# dolinesch.net
KiCad netlist of a schematic drawn in Altium Designer
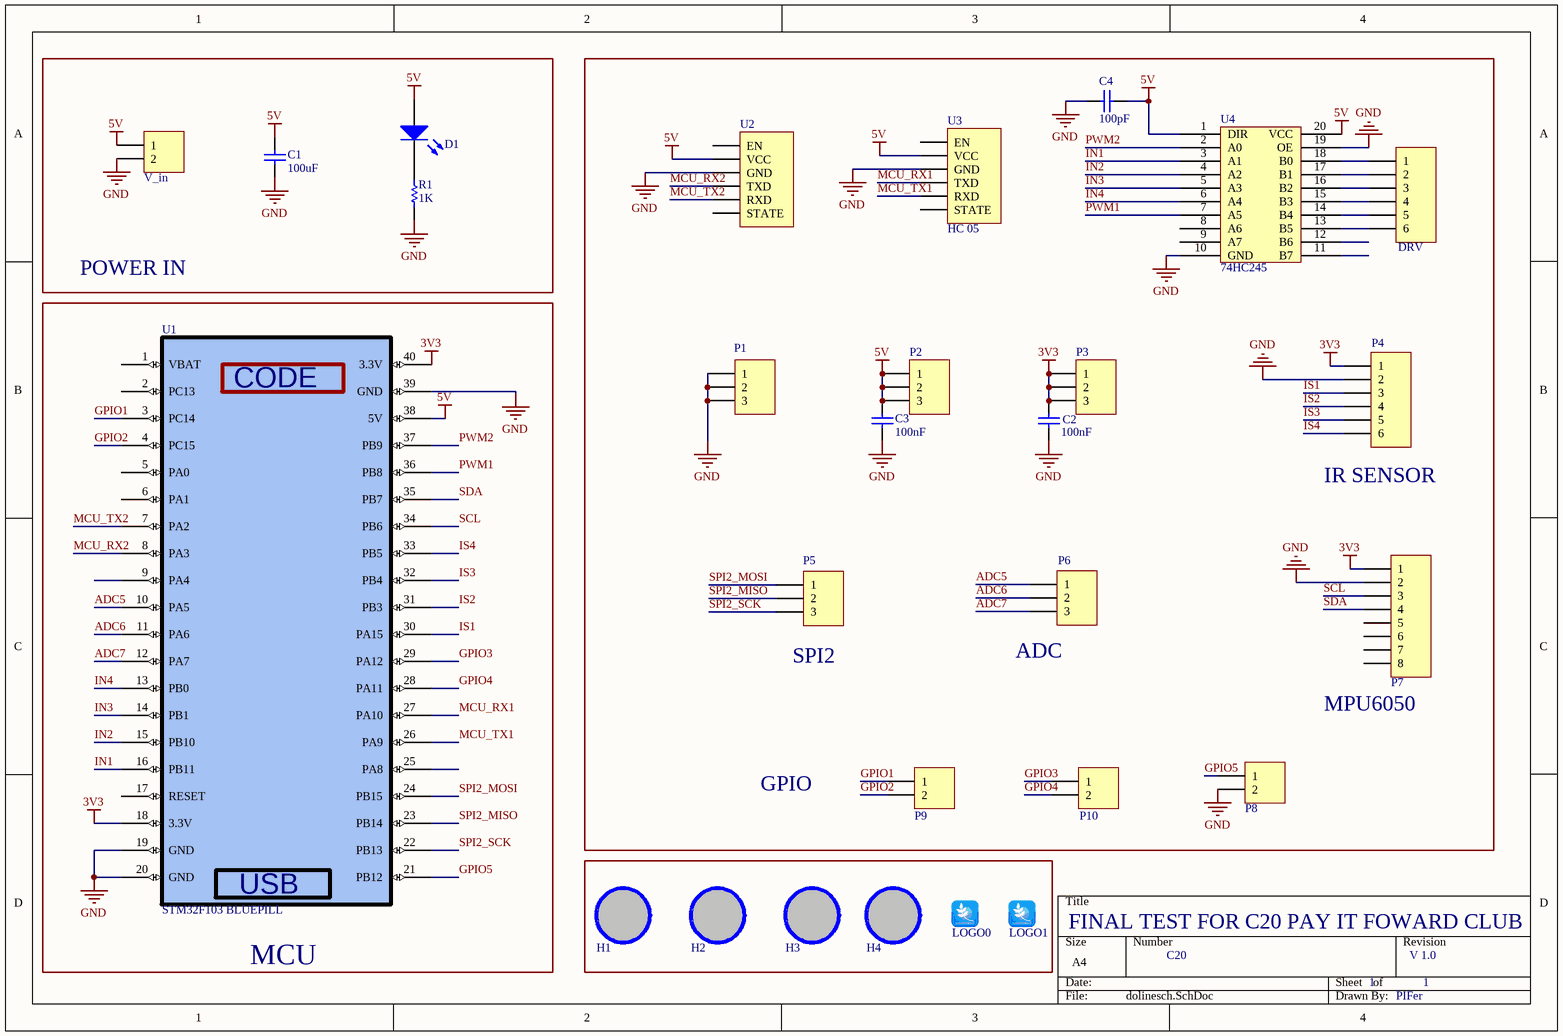
[diagram p0: dolinesch.SchDoc]

(export (version "E")
  (design (tool "Eeschema 10.0.6"))
  (components
    (comp (ref "C1")
      (value "100uF")
      (footprint "CAP-SM-0805")
      (description "Capacitor")
      (fields (field (name "Comment") "Cap Non-Pol SMD"))
      (libsource (lib "PIF_Schematic_Lib") (part "Cap Non-Pol SMD"))
    )
    (comp (ref "C2")
      (value "100nF")
      (footprint "CAP-SM-0805")
      (description "Capacitor")
      (fields (field (name "Comment") "Cap Non-Pol SMD"))
      (libsource (lib "PIF_Schematic_Lib") (part "Cap Non-Pol SMD"))
    )
    (comp (ref "C3")
      (value "100nF")
      (footprint "CAP-SM-0805")
      (description "Capacitor")
      (fields (field (name "Comment") "Cap Non-Pol SMD"))
      (libsource (lib "PIF_Schematic_Lib") (part "Cap Non-Pol SMD"))
    )
    (comp (ref "C4")
      (value "100pF")
      (footprint "CAP-SM-0805")
      (description "Capacitor")
      (fields (field (name "Comment") "Cap Non-Pol SMD"))
      (libsource (lib "PIF_Schematic_Lib") (part "Cap Non-Pol SMD"))
    )
    (comp (ref "D1") (value "LED") (footprint "LED-3mm") (libsource (lib "PIF_Schematic_Lib") (part "LED")))
    (comp (ref "DRV")
      (value "Header 6")
      (footprint "JP6")
      (description "Header, 6-Pin")
      (fields (field (name "PUBLISHER") "Altium Limited"))
      (libsource (lib "PIF_Schematic_Lib") (part "Header 6"))
    )
    (comp (ref "H1")
      (value "Hole")
      (footprint "LO KHOAN 3MM")
      (description "Hole 3mm")
      (libsource (lib "PIF_Schematic_Lib") (part "Hole"))
    )
    (comp (ref "H2")
      (value "Hole")
      (footprint "LO KHOAN 3MM")
      (description "Hole 3mm")
      (libsource (lib "PIF_Schematic_Lib") (part "Hole"))
    )
    (comp (ref "H3")
      (value "Hole")
      (footprint "LO KHOAN 3MM")
      (description "Hole 3mm")
      (libsource (lib "PIF_Schematic_Lib") (part "Hole"))
    )
    (comp (ref "H4")
      (value "Hole")
      (footprint "LO KHOAN 3MM")
      (description "Hole 3mm")
      (libsource (lib "PIF_Schematic_Lib") (part "Hole"))
    )
    (comp (ref "LOGO0")
      (value "LOGO PIF")
      (footprint "PIF LOGO BOTTOM LAYER")
      (libsource (lib "PIF_Schematic_Lib") (part "LOGO PIF_2"))
    )
    (comp (ref "LOGO1")
      (value "LOGO PIF")
      (footprint "PIF LOGO TOP OVERLAY")
      (libsource (lib "PIF_Schematic_Lib") (part "LOGO PIF_2"))
    )
    (comp (ref "P1")
      (value "Header 3")
      (footprint "JP3")
      (description "Header, 3-Pin")
      (fields (field (name "PUBLISHER") "Altium Limited"))
      (libsource (lib "PIF_Schematic_Lib") (part "Header 3"))
    )
    (comp (ref "P2")
      (value "Header 3")
      (footprint "JP3")
      (description "Header, 3-Pin")
      (fields (field (name "PUBLISHER") "Altium Limited"))
      (libsource (lib "PIF_Schematic_Lib") (part "Header 3"))
    )
    (comp (ref "P3")
      (value "Header 3")
      (footprint "JP3")
      (description "Header, 3-Pin")
      (fields (field (name "PUBLISHER") "Altium Limited"))
      (libsource (lib "PIF_Schematic_Lib") (part "Header 3"))
    )
    (comp (ref "P4")
      (value "Header 6")
      (footprint "JP6")
      (description "Header, 6-Pin")
      (fields (field (name "PUBLISHER") "Altium Limited"))
      (libsource (lib "PIF_Schematic_Lib") (part "Header 6"))
    )
    (comp (ref "P5")
      (value "Header 3")
      (footprint "JP3")
      (description "Header, 3-Pin")
      (fields (field (name "PUBLISHER") "Altium Limited"))
      (libsource (lib "PIF_Schematic_Lib") (part "Header 3"))
    )
    (comp (ref "P6")
      (value "Header 3")
      (footprint "JP3")
      (description "Header, 3-Pin")
      (fields (field (name "PUBLISHER") "Altium Limited"))
      (libsource (lib "PIF_Schematic_Lib") (part "Header 3"))
    )
    (comp (ref "P7")
      (value "Header 8")
      (footprint "JP8")
      (description "Header, 8-Pin")
      (fields (field (name "PUBLISHER") "Altium Limited"))
      (libsource (lib "PIF_Schematic_Lib") (part "Header 8"))
    )
    (comp (ref "P8")
      (value "Header 2")
      (footprint "JP2")
      (description "Header, 2-Pin")
      (fields (field (name "PUBLISHER") "Altium Limited"))
      (libsource (lib "PIF_Schematic_Lib") (part "Header 2"))
    )
    (comp (ref "P9")
      (value "Header 2")
      (footprint "JP2")
      (description "Header, 2-Pin")
      (fields (field (name "PUBLISHER") "Altium Limited"))
      (libsource (lib "PIF_Schematic_Lib") (part "Header 2"))
    )
    (comp (ref "P10")
      (value "Header 2")
      (footprint "JP2")
      (description "Header, 2-Pin")
      (fields (field (name "PUBLISHER") "Altium Limited"))
      (libsource (lib "PIF_Schematic_Lib") (part "Header 2"))
    )
    (comp (ref "R1")
      (value "1K")
      (footprint "RES-SM-0603")
      (description "Resistor")
      (fields (field (name "Comment") "RESISTOR SMD"))
      (libsource (lib "PIF_Schematic_Lib") (part "RESISTOR SMD"))
    )
    (comp (ref "U1")
      (value "STM32F103 BLUEPILL")
      (footprint "STM32F103 Bluepill")
      (libsource (lib "PIF_Schematic_Lib") (part "STM32F103 BLUEPILL"))
    )
    (comp (ref "U2") (value "UART") (footprint "JP6") (libsource (lib "PIF_Schematic_Lib") (part "HC 05")))
    (comp (ref "U3") (value "HC 05") (footprint "JP6") (libsource (lib "PIF_Schematic_Lib") (part "HC 05")))
    (comp (ref "U4")
      (value "74HC245")
      (footprint "DIP20/W0.3")
      (description "Octal bus tranceiver")
      (libsource (lib "PIF_Schematic_Lib") (part "74HC245"))
    )
    (comp (ref "V_in")
      (value "Domino 2")
      (footprint "DOMINO 2- 5mm")
      (description "Domino, 2-Pin")
      (fields (field (name "PUBLISHER") "Altium Limited"))
      (libsource (lib "linecarc20_balancing") (part "Domino 2"))
    )
  )
  (nets
    (net (code "1") (name "/ADC5") (class "Default")
      (node (ref "P6") (pin "1") (pinfunction "1_1") (pintype "passive"))
      (node (ref "U1") (pin "10") (pinfunction "PA5_10") (pintype "bidirectional"))
    )
    (net (code "2") (name "/ADC6") (class "Default")
      (node (ref "P6") (pin "2") (pinfunction "2_2") (pintype "passive"))
      (node (ref "U1") (pin "11") (pinfunction "PA6_11") (pintype "bidirectional"))
    )
    (net (code "3") (name "/ADC7") (class "Default")
      (node (ref "P6") (pin "3") (pinfunction "3_3") (pintype "passive"))
      (node (ref "U1") (pin "12") (pinfunction "PA7_12") (pintype "bidirectional"))
    )
    (net (code "4") (name "/GPIO1") (class "Default")
      (node (ref "P9") (pin "1") (pinfunction "1_1") (pintype "passive"))
      (node (ref "U1") (pin "3") (pinfunction "PC14_3") (pintype "bidirectional"))
    )
    (net (code "5") (name "/GPIO2") (class "Default")
      (node (ref "P9") (pin "2") (pinfunction "2_2") (pintype "passive"))
      (node (ref "U1") (pin "4") (pinfunction "PC15_4") (pintype "bidirectional"))
    )
    (net (code "6") (name "/GPIO3") (class "Default")
      (node (ref "P10") (pin "1") (pinfunction "1_1") (pintype "passive"))
      (node (ref "U1") (pin "29") (pinfunction "PA12_29") (pintype "bidirectional"))
    )
    (net (code "7") (name "/GPIO4") (class "Default")
      (node (ref "P10") (pin "2") (pinfunction "2_2") (pintype "passive"))
      (node (ref "U1") (pin "28") (pinfunction "PA11_28") (pintype "bidirectional"))
    )
    (net (code "8") (name "/GPIO5") (class "Default")
      (node (ref "P8") (pin "1") (pinfunction "1_1") (pintype "passive"))
      (node (ref "U1") (pin "21") (pinfunction "PB12_21") (pintype "bidirectional"))
    )
    (net (code "9") (name "/IN1") (class "Default")
      (node (ref "U1") (pin "16") (pinfunction "PB11_16") (pintype "bidirectional"))
      (node (ref "U4") (pin "3") (pinfunction "A1_3") (pintype "passive"))
    )
    (net (code "10") (name "/IN2") (class "Default")
      (node (ref "U1") (pin "15") (pinfunction "PB10_15") (pintype "bidirectional"))
      (node (ref "U4") (pin "4") (pinfunction "A2_4") (pintype "passive"))
    )
    (net (code "11") (name "/IN3") (class "Default")
      (node (ref "U1") (pin "14") (pinfunction "PB1_14") (pintype "bidirectional"))
      (node (ref "U4") (pin "5") (pinfunction "A3_5") (pintype "passive"))
    )
    (net (code "12") (name "/IN4") (class "Default")
      (node (ref "U1") (pin "13") (pinfunction "PB0_13") (pintype "bidirectional"))
      (node (ref "U4") (pin "6") (pinfunction "A4_6") (pintype "passive"))
    )
    (net (code "13") (name "/IS1") (class "Default")
      (node (ref "P4") (pin "3") (pinfunction "3_3") (pintype "passive"))
      (node (ref "U1") (pin "30") (pinfunction "PA15_30") (pintype "bidirectional"))
    )
    (net (code "14") (name "/IS2") (class "Default")
      (node (ref "P4") (pin "4") (pinfunction "4_4") (pintype "passive"))
      (node (ref "U1") (pin "31") (pinfunction "PB3_31") (pintype "bidirectional"))
    )
    (net (code "15") (name "/IS3") (class "Default")
      (node (ref "P4") (pin "5") (pinfunction "5_5") (pintype "passive"))
      (node (ref "U1") (pin "32") (pinfunction "PB4_32") (pintype "bidirectional"))
    )
    (net (code "16") (name "/IS4") (class "Default")
      (node (ref "P4") (pin "6") (pinfunction "6_6") (pintype "passive"))
      (node (ref "U1") (pin "33") (pinfunction "PB5_33") (pintype "bidirectional"))
    )
    (net (code "17") (name "/MCU_RX1") (class "Default")
      (node (ref "U1") (pin "27") (pinfunction "PA10_27") (pintype "bidirectional"))
      (node (ref "U3") (pin "4") (pinfunction "TXD_4") (pintype "passive"))
    )
    (net (code "18") (name "/MCU_RX2") (class "Default")
      (node (ref "U1") (pin "8") (pinfunction "PA3_8") (pintype "bidirectional"))
      (node (ref "U2") (pin "4") (pinfunction "TXD_4") (pintype "passive"))
    )
    (net (code "19") (name "/MCU_TX1") (class "Default")
      (node (ref "U1") (pin "26") (pinfunction "PA9_26") (pintype "bidirectional"))
      (node (ref "U3") (pin "5") (pinfunction "RXD_5") (pintype "passive"))
    )
    (net (code "20") (name "/MCU_TX2") (class "Default")
      (node (ref "U1") (pin "7") (pinfunction "PA2_7") (pintype "bidirectional"))
      (node (ref "U2") (pin "5") (pinfunction "RXD_5") (pintype "passive"))
    )
    (net (code "21") (name "/PWM1") (class "Default")
      (node (ref "U1") (pin "36") (pinfunction "PB8_36") (pintype "bidirectional"))
      (node (ref "U4") (pin "7") (pinfunction "A5_7") (pintype "passive"))
    )
    (net (code "22") (name "/PWM2") (class "Default")
      (node (ref "U1") (pin "37") (pinfunction "PB9_37") (pintype "bidirectional"))
      (node (ref "U4") (pin "2") (pinfunction "A0_2") (pintype "passive"))
    )
    (net (code "23") (name "/SCL") (class "Default")
      (node (ref "P7") (pin "3") (pinfunction "3_3") (pintype "passive"))
      (node (ref "U1") (pin "34") (pinfunction "PB6_34") (pintype "bidirectional"))
    )
    (net (code "24") (name "/SDA") (class "Default")
      (node (ref "P7") (pin "4") (pinfunction "4_4") (pintype "passive"))
      (node (ref "U1") (pin "35") (pinfunction "PB7_35") (pintype "bidirectional"))
    )
    (net (code "25") (name "/SPI2_MISO") (class "Default")
      (node (ref "P5") (pin "2") (pinfunction "2_2") (pintype "passive"))
      (node (ref "U1") (pin "23") (pinfunction "PB14_23") (pintype "bidirectional"))
    )
    (net (code "26") (name "/SPI2_MOSI") (class "Default")
      (node (ref "P5") (pin "1") (pinfunction "1_1") (pintype "passive"))
      (node (ref "U1") (pin "24") (pinfunction "PB15_24") (pintype "bidirectional"))
    )
    (net (code "27") (name "/SPI2_SCK") (class "Default")
      (node (ref "P5") (pin "3") (pinfunction "3_3") (pintype "passive"))
      (node (ref "U1") (pin "22") (pinfunction "PB13_22") (pintype "bidirectional"))
    )
    (net (code "28") (name "3V3") (class "Default")
      (node (ref "C2") (pin "2") (pinfunction "2_2") (pintype "passive"))
      (node (ref "P3") (pin "1") (pinfunction "1_1") (pintype "passive"))
      (node (ref "P3") (pin "2") (pinfunction "2_2") (pintype "passive"))
      (node (ref "P3") (pin "3") (pinfunction "3_3") (pintype "passive"))
      (node (ref "P4") (pin "1") (pinfunction "1_1") (pintype "passive"))
      (node (ref "P7") (pin "1") (pinfunction "1_1") (pintype "passive"))
      (node (ref "U1") (pin "18") (pinfunction "3.3V_18") (pintype "bidirectional"))
      (node (ref "U1") (pin "40") (pinfunction "3.3V_40") (pintype "bidirectional"))
    )
    (net (code "29") (name "5V") (class "Default")
      (node (ref "C1") (pin "2") (pinfunction "2_2") (pintype "passive"))
      (node (ref "C3") (pin "2") (pinfunction "2_2") (pintype "passive"))
      (node (ref "C4") (pin "2") (pinfunction "2_2") (pintype "passive"))
      (node (ref "D1") (pin "1") (pinfunction "A_1") (pintype "passive"))
      (node (ref "P2") (pin "1") (pinfunction "1_1") (pintype "passive"))
      (node (ref "P2") (pin "2") (pinfunction "2_2") (pintype "passive"))
      (node (ref "P2") (pin "3") (pinfunction "3_3") (pintype "passive"))
      (node (ref "U1") (pin "38") (pinfunction "5V_38") (pintype "bidirectional"))
      (node (ref "U2") (pin "2") (pinfunction "VCC_2") (pintype "passive"))
      (node (ref "U3") (pin "2") (pinfunction "VCC_2") (pintype "passive"))
      (node (ref "U4") (pin "1") (pinfunction "DIR_1") (pintype "passive"))
      (node (ref "U4") (pin "20") (pinfunction "VCC_20") (pintype "power_in"))
      (node (ref "V_in") (pin "1") (pinfunction "1_1") (pintype "passive"))
    )
    (net (code "30") (name "GND") (class "Default")
      (node (ref "C1") (pin "1") (pinfunction "1_1") (pintype "passive"))
      (node (ref "C2") (pin "1") (pinfunction "1_1") (pintype "passive"))
      (node (ref "C3") (pin "1") (pinfunction "1_1") (pintype "passive"))
      (node (ref "C4") (pin "1") (pinfunction "1_1") (pintype "passive"))
      (node (ref "P1") (pin "1") (pinfunction "1_1") (pintype "passive"))
      (node (ref "P1") (pin "2") (pinfunction "2_2") (pintype "passive"))
      (node (ref "P1") (pin "3") (pinfunction "3_3") (pintype "passive"))
      (node (ref "P4") (pin "2") (pinfunction "2_2") (pintype "passive"))
      (node (ref "P7") (pin "2") (pinfunction "2_2") (pintype "passive"))
      (node (ref "P8") (pin "2") (pinfunction "2_2") (pintype "passive"))
      (node (ref "R1") (pin "2") (pinfunction "2_2") (pintype "passive"))
      (node (ref "U1") (pin "19") (pinfunction "GND_19") (pintype "bidirectional"))
      (node (ref "U1") (pin "20") (pinfunction "GND_20") (pintype "bidirectional"))
      (node (ref "U1") (pin "39") (pinfunction "GND_39") (pintype "bidirectional"))
      (node (ref "U2") (pin "3") (pinfunction "GND_3") (pintype "passive"))
      (node (ref "U3") (pin "3") (pinfunction "GND_3") (pintype "passive"))
      (node (ref "U4") (pin "10") (pinfunction "GND_10") (pintype "power_in"))
      (node (ref "U4") (pin "19") (pinfunction "OE_19") (pintype "passive"))
      (node (ref "V_in") (pin "2") (pinfunction "2_2") (pintype "passive"))
    )
    (net (code "31") (name "Net-(D1-K)") (class "Default")
      (node (ref "D1") (pin "2") (pinfunction "K_2") (pintype "passive"))
      (node (ref "R1") (pin "1") (pinfunction "1_1") (pintype "passive"))
    )
    (net (code "32") (name "Net-(U4-B0)") (class "Default")
      (node (ref "DRV") (pin "1") (pinfunction "1_1") (pintype "passive"))
      (node (ref "U4") (pin "18") (pinfunction "B0_18") (pintype "passive"))
    )
    (net (code "33") (name "Net-(U4-B1)") (class "Default")
      (node (ref "DRV") (pin "2") (pinfunction "2_2") (pintype "passive"))
      (node (ref "U4") (pin "17") (pinfunction "B1_17") (pintype "passive"))
    )
    (net (code "34") (name "Net-(U4-B2)") (class "Default")
      (node (ref "DRV") (pin "3") (pinfunction "3_3") (pintype "passive"))
      (node (ref "U4") (pin "16") (pinfunction "B2_16") (pintype "passive"))
    )
    (net (code "35") (name "Net-(U4-B3)") (class "Default")
      (node (ref "DRV") (pin "4") (pinfunction "4_4") (pintype "passive"))
      (node (ref "U4") (pin "15") (pinfunction "B3_15") (pintype "passive"))
    )
    (net (code "36") (name "Net-(U4-B4)") (class "Default")
      (node (ref "DRV") (pin "5") (pinfunction "5_5") (pintype "passive"))
      (node (ref "U4") (pin "14") (pinfunction "B4_14") (pintype "passive"))
    )
    (net (code "37") (name "Net-(U4-B5)") (class "Default")
      (node (ref "DRV") (pin "6") (pinfunction "6_6") (pintype "passive"))
      (node (ref "U4") (pin "13") (pinfunction "B5_13") (pintype "passive"))
    )
    (net (code "38") (name "unconnected-(H1-Pad1)") (class "Default")
      (node (ref "H1") (pin "1") (pinfunction "1_1") (pintype "passive"))
    )
    (net (code "39") (name "unconnected-(H2-Pad1)") (class "Default")
      (node (ref "H2") (pin "1") (pinfunction "1_1") (pintype "passive"))
    )
    (net (code "40") (name "unconnected-(H3-Pad1)") (class "Default")
      (node (ref "H3") (pin "1") (pinfunction "1_1") (pintype "passive"))
    )
    (net (code "41") (name "unconnected-(H4-Pad1)") (class "Default")
      (node (ref "H4") (pin "1") (pinfunction "1_1") (pintype "passive"))
    )
    (net (code "42") (name "unconnected-(P7-Pad5)") (class "Default")
      (node (ref "P7") (pin "5") (pinfunction "5_5") (pintype "passive"))
    )
    (net (code "43") (name "unconnected-(P7-Pad6)") (class "Default")
      (node (ref "P7") (pin "6") (pinfunction "6_6") (pintype "passive"))
    )
    (net (code "44") (name "unconnected-(P7-Pad7)") (class "Default")
      (node (ref "P7") (pin "7") (pinfunction "7_7") (pintype "passive"))
    )
    (net (code "45") (name "unconnected-(P7-Pad8)") (class "Default")
      (node (ref "P7") (pin "8") (pinfunction "8_8") (pintype "passive"))
    )
    (net (code "46") (name "unconnected-(U1-PA0-Pad5)") (class "Default")
      (node (ref "U1") (pin "5") (pinfunction "PA0_5") (pintype "bidirectional"))
    )
    (net (code "47") (name "unconnected-(U1-PA1-Pad6)") (class "Default")
      (node (ref "U1") (pin "6") (pinfunction "PA1_6") (pintype "bidirectional"))
    )
    (net (code "48") (name "unconnected-(U1-PA4-Pad9)") (class "Default")
      (node (ref "U1") (pin "9") (pinfunction "PA4_9") (pintype "bidirectional"))
    )
    (net (code "49") (name "unconnected-(U1-PA8-Pad25)") (class "Default")
      (node (ref "U1") (pin "25") (pinfunction "PA8_25") (pintype "bidirectional"))
    )
    (net (code "50") (name "unconnected-(U1-PC13-Pad2)") (class "Default")
      (node (ref "U1") (pin "2") (pinfunction "PC13_2") (pintype "bidirectional"))
    )
    (net (code "51") (name "unconnected-(U1-RESET-Pad17)") (class "Default")
      (node (ref "U1") (pin "17") (pinfunction "RESET_17") (pintype "bidirectional"))
    )
    (net (code "52") (name "unconnected-(U1-VBAT-Pad1)") (class "Default")
      (node (ref "U1") (pin "1") (pinfunction "VBAT_1") (pintype "bidirectional"))
    )
    (net (code "53") (name "unconnected-(U2-EN-Pad1)") (class "Default")
      (node (ref "U2") (pin "1") (pinfunction "EN_1") (pintype "passive"))
    )
    (net (code "54") (name "unconnected-(U2-STATE-Pad6)") (class "Default")
      (node (ref "U2") (pin "6") (pinfunction "STATE_6") (pintype "passive"))
    )
    (net (code "55") (name "unconnected-(U3-EN-Pad1)") (class "Default")
      (node (ref "U3") (pin "1") (pinfunction "EN_1") (pintype "passive"))
    )
    (net (code "56") (name "unconnected-(U3-STATE-Pad6)") (class "Default")
      (node (ref "U3") (pin "6") (pinfunction "STATE_6") (pintype "passive"))
    )
    (net (code "57") (name "unconnected-(U4-A6-Pad8)") (class "Default")
      (node (ref "U4") (pin "8") (pinfunction "A6_8") (pintype "passive"))
    )
    (net (code "58") (name "unconnected-(U4-A7-Pad9)") (class "Default")
      (node (ref "U4") (pin "9") (pinfunction "A7_9") (pintype "passive"))
    )
    (net (code "59") (name "unconnected-(U4-B6-Pad12)") (class "Default")
      (node (ref "U4") (pin "12") (pinfunction "B6_12") (pintype "passive"))
    )
    (net (code "60") (name "unconnected-(U4-B7-Pad11)") (class "Default")
      (node (ref "U4") (pin "11") (pinfunction "B7_11") (pintype "passive"))
    )
  )
)
